# Catdoor-TwoMosfet-FeatherWing.net
KiCad netlist of a schematic drawn in EAGLE
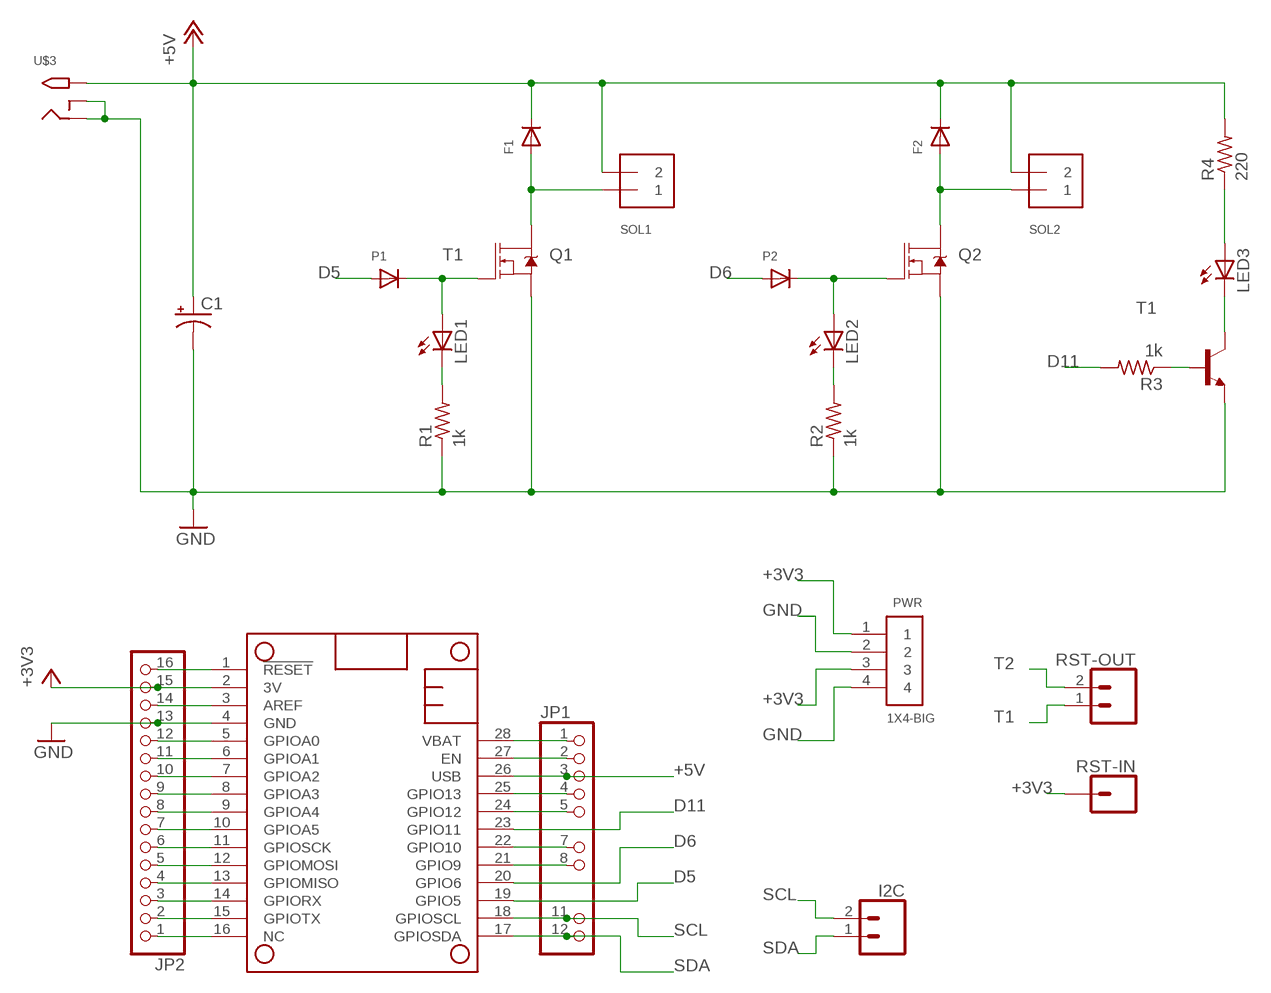
[diagram p0: schematic, sheet 1]

(export (version "E")
  (design (tool "Eeschema 10.0.6"))
  (components
    (comp (ref "C1")
      (value "CPOL-USE5-13")
      (footprint "eagle-import:E5-13")
      (libsource (lib "eagle-import") (part "CPOL-USE5-13"))
    )
    (comp (ref "F1")
      (value "DIODELONG-SPACING")
      (footprint "eagle-import:DIODE-LONG")
      (libsource (lib "eagle-import") (part "DIODELONG-SPACING"))
    )
    (comp (ref "F2")
      (value "DIODELONG-SPACING")
      (footprint "eagle-import:DIODE-LONG")
      (libsource (lib "eagle-import") (part "DIODELONG-SPACING"))
    )
    (comp (ref "I2C")
      (value "CONN_02")
      (footprint "eagle-import:1X02")
      (libsource (lib "eagle-import") (part "CONN_02"))
    )
    (comp (ref "JP1")
      (value "PINHD-1X12-CB")
      (footprint "eagle-import:1X12-CB")
      (libsource (lib "eagle-import") (part "PINHD-1X12-CB"))
    )
    (comp (ref "JP2")
      (value "HEADER-1X16ROUND")
      (footprint "eagle-import:1X16_ROUND")
      (libsource (lib "eagle-import") (part "HEADER-1X16ROUND"))
    )
    (comp (ref "LED1")
      (value "LED3MM")
      (footprint "eagle-import:LED3MM")
      (libsource (lib "eagle-import") (part "LED3MM"))
    )
    (comp (ref "LED2")
      (value "LED3MM")
      (footprint "eagle-import:LED3MM")
      (libsource (lib "eagle-import") (part "LED3MM"))
    )
    (comp (ref "LED3")
      (value "LED3MM")
      (footprint "eagle-import:LED3MM")
      (libsource (lib "eagle-import") (part "LED3MM"))
    )
    (comp (ref "MS1")
      (value "FEATHERWING")
      (footprint "eagle-import:FEATHERWING")
      (libsource (lib "eagle-import") (part "FEATHERWING"))
    )
    (comp (ref "P1")
      (value "DIODELONG-SPACING")
      (footprint "eagle-import:DIODE-LONG")
      (libsource (lib "eagle-import") (part "DIODELONG-SPACING"))
    )
    (comp (ref "P2")
      (value "DIODELONG-SPACING")
      (footprint "eagle-import:DIODE-LONG")
      (libsource (lib "eagle-import") (part "DIODELONG-SPACING"))
    )
    (comp (ref "PWR")
      (value "1X4-BIG")
      (footprint "eagle-import:1X04-BIG")
      (libsource (lib "eagle-import") (part "1X4-BIG"))
    )
    (comp (ref "Q1")
      (value "MOSFET-NCH-FQP30N06L")
      (footprint "eagle-import:TO220V")
      (libsource (lib "eagle-import") (part "MOSFET-NCH-FQP30N06L"))
    )
    (comp (ref "Q2")
      (value "MOSFET-NCH-FQP30N06L")
      (footprint "eagle-import:TO220V")
      (libsource (lib "eagle-import") (part "MOSFET-NCH-FQP30N06L"))
    )
    (comp (ref "R1")
      (value "1k")
      (footprint "eagle-import:0204_7")
      (libsource (lib "eagle-import") (part "R-US_0204/7"))
    )
    (comp (ref "R2")
      (value "1k")
      (footprint "eagle-import:0204_7")
      (libsource (lib "eagle-import") (part "R-US_0204/7"))
    )
    (comp (ref "R3")
      (value "1k")
      (footprint "eagle-import:0204_7")
      (libsource (lib "eagle-import") (part "R-US_0204/7"))
    )
    (comp (ref "R4")
      (value "220")
      (footprint "eagle-import:0204_7")
      (libsource (lib "eagle-import") (part "R-US_0204/7"))
    )
    (comp (ref "RST-IN")
      (value "CONN_01")
      (footprint "eagle-import:1X01")
      (libsource (lib "eagle-import") (part "CONN_01"))
    )
    (comp (ref "RST-OUT")
      (value "CONN_02")
      (footprint "eagle-import:1X02")
      (libsource (lib "eagle-import") (part "CONN_02"))
    )
    (comp (ref "SOL1")
      (value "TERMBLOCK_1X2")
      (footprint "eagle-import:TERMBLOCK_1X2-3.5MM")
      (libsource (lib "eagle-import") (part "TERMBLOCK_1X2"))
    )
    (comp (ref "SOL2")
      (value "TERMBLOCK_1X2")
      (footprint "eagle-import:TERMBLOCK_1X2-3.5MM")
      (libsource (lib "eagle-import") (part "TERMBLOCK_1X2"))
    )
    (comp (ref "T1")
      (value "2N2222")
      (footprint "eagle-import:TO92-EBC-OVAL")
      (libsource (lib "eagle-import") (part "2N2222"))
    )
    (comp (ref "U$3")
      (value "2.1MMJACKTHM")
      (footprint "eagle-import:PJ-102A")
      (libsource (lib "eagle-import") (part "2.1MMJACKTHM"))
    )
  )
  (nets
    (net (code "1") (name "+3V3") (class "Default")
      (node (ref "JP2") (pin "15") (pinfunction "15_15") (pintype "passive"))
      (node (ref "MS1") (pin "2") (pinfunction "3V_2") (pintype "power_in"))
      (node (ref "PWR") (pin "1") (pinfunction "1_1") (pintype "bidirectional"))
      (node (ref "PWR") (pin "3") (pinfunction "3_3") (pintype "bidirectional"))
      (node (ref "RST-IN") (pin "1") (pinfunction "1_1") (pintype "passive"))
    )
    (net (code "2") (name "+5V") (class "Default")
      (node (ref "C1") (pin "+") (pinfunction "+_+") (pintype "passive"))
      (node (ref "F1") (pin "C") (pinfunction "C_C") (pintype "passive"))
      (node (ref "F2") (pin "C") (pinfunction "C_C") (pintype "passive"))
      (node (ref "JP1") (pin "3") (pinfunction "3_3") (pintype "passive"))
      (node (ref "MS1") (pin "26") (pinfunction "USB_26") (pintype "power_in"))
      (node (ref "R4") (pin "2") (pinfunction "2_2") (pintype "passive"))
      (node (ref "SOL1") (pin "2") (pinfunction "2_2") (pintype "passive"))
      (node (ref "SOL2") (pin "2") (pinfunction "2_2") (pintype "passive"))
      (node (ref "U$3") (pin "TIP") (pinfunction "TIP_TIP") (pintype "bidirectional"))
    )
    (net (code "3") (name "/D5") (class "Default")
      (node (ref "MS1") (pin "19") (pinfunction "GPIO5_19") (pintype "bidirectional"))
      (node (ref "P1") (pin "A") (pinfunction "A_A") (pintype "passive"))
    )
    (net (code "4") (name "/D6") (class "Default")
      (node (ref "MS1") (pin "20") (pinfunction "GPIO6_20") (pintype "bidirectional"))
      (node (ref "P2") (pin "A") (pinfunction "A_A") (pintype "passive"))
    )
    (net (code "5") (name "/D11") (class "Default")
      (node (ref "MS1") (pin "23") (pinfunction "GPIO11_23") (pintype "bidirectional"))
      (node (ref "R3") (pin "2") (pinfunction "2_2") (pintype "passive"))
    )
    (net (code "6") (name "/SCL") (class "Default")
      (node (ref "I2C") (pin "2") (pinfunction "2_2") (pintype "passive"))
      (node (ref "JP1") (pin "11") (pinfunction "11_11") (pintype "passive"))
      (node (ref "MS1") (pin "18") (pinfunction "GPIOSCL_18") (pintype "bidirectional"))
    )
    (net (code "7") (name "/SDA") (class "Default")
      (node (ref "I2C") (pin "1") (pinfunction "1_1") (pintype "passive"))
      (node (ref "JP1") (pin "12") (pinfunction "12_12") (pintype "passive"))
      (node (ref "MS1") (pin "17") (pinfunction "GPIOSDA_17") (pintype "bidirectional"))
    )
    (net (code "8") (name "/T1") (class "Default")
      (node (ref "LED1") (pin "A") (pinfunction "A_A") (pintype "passive"))
      (node (ref "P1") (pin "C") (pinfunction "C_C") (pintype "passive"))
      (node (ref "Q1") (pin "1") (pinfunction "G_1") (pintype "bidirectional"))
      (node (ref "RST-OUT") (pin "1") (pinfunction "1_1") (pintype "passive"))
    )
    (net (code "9") (name "/T2") (class "Default")
      (node (ref "LED2") (pin "A") (pinfunction "A_A") (pintype "passive"))
      (node (ref "P2") (pin "C") (pinfunction "C_C") (pintype "passive"))
      (node (ref "Q2") (pin "1") (pinfunction "G_1") (pintype "bidirectional"))
      (node (ref "RST-OUT") (pin "2") (pinfunction "2_2") (pintype "passive"))
    )
    (net (code "10") (name "GND") (class "Default")
      (node (ref "C1") (pin "-") (pinfunction "-_-") (pintype "passive"))
      (node (ref "JP2") (pin "13") (pinfunction "13_13") (pintype "passive"))
      (node (ref "MS1") (pin "4") (pinfunction "GND_4") (pintype "power_in"))
      (node (ref "PWR") (pin "2") (pinfunction "2_2") (pintype "bidirectional"))
      (node (ref "PWR") (pin "4") (pinfunction "4_4") (pintype "bidirectional"))
      (node (ref "Q1") (pin "3") (pinfunction "S_3") (pintype "bidirectional"))
      (node (ref "Q2") (pin "3") (pinfunction "S_3") (pintype "bidirectional"))
      (node (ref "R1") (pin "1") (pinfunction "1_1") (pintype "passive"))
      (node (ref "R2") (pin "1") (pinfunction "1_1") (pintype "passive"))
      (node (ref "T1") (pin "E") (pinfunction "E_E") (pintype "passive"))
      (node (ref "U$3") (pin "RING") (pinfunction "RING_RING") (pintype "bidirectional"))
      (node (ref "U$3") (pin "RING_SW") (pinfunction "RING_SW_RING_SW") (pintype "bidirectional"))
    )
    (net (code "11") (name "Net-(LED1-C)") (class "Default")
      (node (ref "LED1") (pin "K") (pinfunction "C_K") (pintype "passive"))
      (node (ref "R1") (pin "2") (pinfunction "2_2") (pintype "passive"))
    )
    (net (code "12") (name "Net-(LED2-C)") (class "Default")
      (node (ref "LED2") (pin "K") (pinfunction "C_K") (pintype "passive"))
      (node (ref "R2") (pin "2") (pinfunction "2_2") (pintype "passive"))
    )
    (net (code "13") (name "Net-(LED3-C)") (class "Default")
      (node (ref "LED3") (pin "K") (pinfunction "C_K") (pintype "passive"))
      (node (ref "T1") (pin "C") (pinfunction "C_C") (pintype "passive"))
    )
    (net (code "14") (name "Net-(LED3-PadA)") (class "Default")
      (node (ref "LED3") (pin "A") (pinfunction "A_A") (pintype "passive"))
      (node (ref "R4") (pin "1") (pinfunction "1_1") (pintype "passive"))
    )
    (net (code "15") (name "Net-(MS1-AREF)") (class "Default")
      (node (ref "JP2") (pin "14") (pinfunction "14_14") (pintype "passive"))
      (node (ref "MS1") (pin "3") (pinfunction "AREF_3") (pintype "passive"))
    )
    (net (code "16") (name "Net-(MS1-EN)") (class "Default")
      (node (ref "JP1") (pin "2") (pinfunction "2_2") (pintype "passive"))
      (node (ref "MS1") (pin "27") (pinfunction "EN_27") (pintype "passive"))
    )
    (net (code "17") (name "Net-(MS1-GPIO9)") (class "Default")
      (node (ref "JP1") (pin "8") (pinfunction "8_8") (pintype "passive"))
      (node (ref "MS1") (pin "21") (pinfunction "GPIO9_21") (pintype "bidirectional"))
    )
    (net (code "18") (name "Net-(MS1-GPIO10)") (class "Default")
      (node (ref "JP1") (pin "7") (pinfunction "7_7") (pintype "passive"))
      (node (ref "MS1") (pin "22") (pinfunction "GPIO10_22") (pintype "bidirectional"))
    )
    (net (code "19") (name "Net-(MS1-GPIO12)") (class "Default")
      (node (ref "JP1") (pin "5") (pinfunction "5_5") (pintype "passive"))
      (node (ref "MS1") (pin "24") (pinfunction "GPIO12_24") (pintype "bidirectional"))
    )
    (net (code "20") (name "Net-(MS1-GPIO13)") (class "Default")
      (node (ref "JP1") (pin "4") (pinfunction "4_4") (pintype "passive"))
      (node (ref "MS1") (pin "25") (pinfunction "GPIO13_25") (pintype "bidirectional"))
    )
    (net (code "21") (name "Net-(MS1-GPIOA0)") (class "Default")
      (node (ref "JP2") (pin "12") (pinfunction "12_12") (pintype "passive"))
      (node (ref "MS1") (pin "5") (pinfunction "GPIOA0_5") (pintype "bidirectional"))
    )
    (net (code "22") (name "Net-(MS1-GPIOA1)") (class "Default")
      (node (ref "JP2") (pin "11") (pinfunction "11_11") (pintype "passive"))
      (node (ref "MS1") (pin "6") (pinfunction "GPIOA1_6") (pintype "bidirectional"))
    )
    (net (code "23") (name "Net-(MS1-GPIOA2)") (class "Default")
      (node (ref "JP2") (pin "10") (pinfunction "10_10") (pintype "passive"))
      (node (ref "MS1") (pin "7") (pinfunction "GPIOA2_7") (pintype "bidirectional"))
    )
    (net (code "24") (name "Net-(MS1-GPIOA3)") (class "Default")
      (node (ref "JP2") (pin "9") (pinfunction "9_9") (pintype "passive"))
      (node (ref "MS1") (pin "8") (pinfunction "GPIOA3_8") (pintype "bidirectional"))
    )
    (net (code "25") (name "Net-(MS1-GPIOA4)") (class "Default")
      (node (ref "JP2") (pin "8") (pinfunction "8_8") (pintype "passive"))
      (node (ref "MS1") (pin "9") (pinfunction "GPIOA4_9") (pintype "bidirectional"))
    )
    (net (code "26") (name "Net-(MS1-GPIOA5)") (class "Default")
      (node (ref "JP2") (pin "7") (pinfunction "7_7") (pintype "passive"))
      (node (ref "MS1") (pin "10") (pinfunction "GPIOA5_10") (pintype "bidirectional"))
    )
    (net (code "27") (name "Net-(MS1-GPIOMISO)") (class "Default")
      (node (ref "JP2") (pin "4") (pinfunction "4_4") (pintype "passive"))
      (node (ref "MS1") (pin "13") (pinfunction "GPIOMISO_13") (pintype "bidirectional"))
    )
    (net (code "28") (name "Net-(MS1-GPIOMOSI)") (class "Default")
      (node (ref "JP2") (pin "5") (pinfunction "5_5") (pintype "passive"))
      (node (ref "MS1") (pin "12") (pinfunction "GPIOMOSI_12") (pintype "bidirectional"))
    )
    (net (code "29") (name "Net-(MS1-GPIORX)") (class "Default")
      (node (ref "JP2") (pin "3") (pinfunction "3_3") (pintype "passive"))
      (node (ref "MS1") (pin "14") (pinfunction "GPIORX_14") (pintype "bidirectional"))
    )
    (net (code "30") (name "Net-(MS1-GPIOSCK)") (class "Default")
      (node (ref "JP2") (pin "6") (pinfunction "6_6") (pintype "passive"))
      (node (ref "MS1") (pin "11") (pinfunction "GPIOSCK_11") (pintype "bidirectional"))
    )
    (net (code "31") (name "Net-(MS1-GPIOTX)") (class "Default")
      (node (ref "JP2") (pin "2") (pinfunction "2_2") (pintype "passive"))
      (node (ref "MS1") (pin "15") (pinfunction "GPIOTX_15") (pintype "bidirectional"))
    )
    (net (code "32") (name "Net-(MS1-NC)") (class "Default")
      (node (ref "JP2") (pin "1") (pinfunction "1_1") (pintype "passive"))
      (node (ref "MS1") (pin "16") (pinfunction "NC_16") (pintype "passive"))
    )
    (net (code "33") (name "Net-(MS1-VBAT)") (class "Default")
      (node (ref "JP1") (pin "1") (pinfunction "1_1") (pintype "passive"))
      (node (ref "MS1") (pin "28") (pinfunction "VBAT_28") (pintype "power_in"))
    )
    (net (code "34") (name "Net-(MS1-~{RESET})") (class "Default")
      (node (ref "JP2") (pin "16") (pinfunction "16_16") (pintype "passive"))
      (node (ref "MS1") (pin "1") (pinfunction "~{RESET}_1") (pintype "input"))
    )
    (net (code "35") (name "Net-(Q1-D)") (class "Default")
      (node (ref "F1") (pin "A") (pinfunction "A_A") (pintype "passive"))
      (node (ref "Q1") (pin "2") (pinfunction "D_2") (pintype "bidirectional"))
      (node (ref "SOL1") (pin "1") (pinfunction "1_1") (pintype "passive"))
    )
    (net (code "36") (name "Net-(Q2-D)") (class "Default")
      (node (ref "F2") (pin "A") (pinfunction "A_A") (pintype "passive"))
      (node (ref "Q2") (pin "2") (pinfunction "D_2") (pintype "bidirectional"))
      (node (ref "SOL2") (pin "1") (pinfunction "1_1") (pintype "passive"))
    )
    (net (code "37") (name "Net-(R3-Pad1)") (class "Default")
      (node (ref "R3") (pin "1") (pinfunction "1_1") (pintype "passive"))
      (node (ref "T1") (pin "B") (pinfunction "B_B") (pintype "passive"))
    )
  )
)
